# nRF52840.net
KiCad netlist of a schematic drawn in Altium Designer
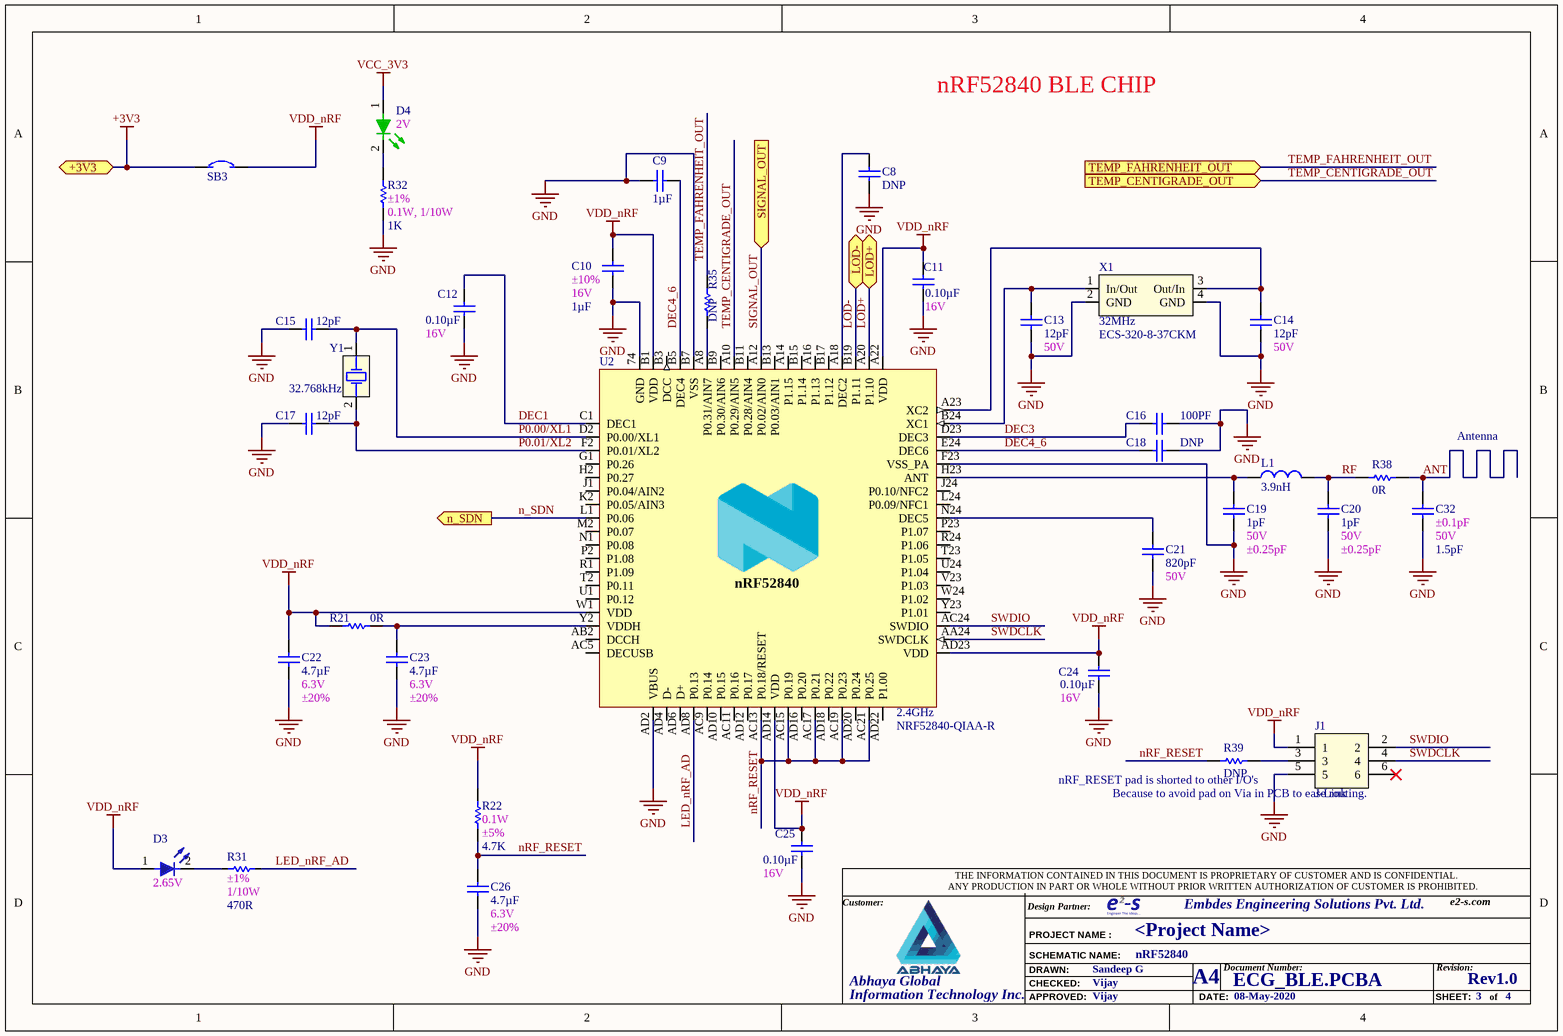
[diagram p0: nRF52840.SchDoc]

(export (version "E")
  (design (tool "Eeschema 10.0.6"))
  (components
    (comp (ref "C8")
      (value "DNP")
      (footprint "SMDC0402")
      (description "CAP CER 100PF 25V C0G/NP0 0402")
      (fields (field (name "MANUFACTURER") "KEMET") (field (name "VENDOR PART NUMBER") "399-1022-1-ND"))
      (libsource (lib "Master_ Library") (part "ECA100P0K25V0-SB"))
    )
    (comp (ref "C9")
      (value "1µF")
      (footprint "SMDC0402")
      (description "CAP CER 1UF 16V X5R 0402")
      (fields
        (field (name "MANUFACTURER") "Samsung Electro-Mechanics")
        (field (name "VENDOR PART NUMBER") "1276-1067-1-ND")
      )
      (libsource (lib "Integrated_Master_Library") (part "ECA1U00L16V0-SB"))
    )
    (comp (ref "C10")
      (value "1µF")
      (footprint "SMDC0402")
      (description "CAP CER 1UF 16V X5R 0402")
      (fields
        (field (name "MANUFACTURER") "Samsung Electro-Mechanics")
        (field (name "VENDOR PART NUMBER") "1276-1067-1-ND")
        (field (name "2ND AUXILIARY FIELD") "±10%")
        (field (name "1ST AUXILIARY FIELD") "16V")
      )
      (libsource (lib "Integrated_Master_Library") (part "ECA1U00L16V0-SB"))
    )
    (comp (ref "C11")
      (value "0.10µF")
      (footprint "SMDC0402")
      (description "CAP CER 0.1UF 16V X7R 0402")
      (fields
        (field (name "MANUFACTURER") "Samsung Electro-Mechanics America, Inc.")
        (field (name "MANUFACTURER PART NUMBER") "CL05B104KO5NNNC")
        (field (name "1ST AUXILIARY FIELD") "16V")
      )
      (libsource (lib "Master_ Library") (part "ECA0U10K16V0-1-SB"))
    )
    (comp (ref "C12")
      (value "0.10µF")
      (footprint "SMDC0402")
      (description "CAP CER 0.1UF 16V X7R 0402")
      (fields
        (field (name "MANUFACTURER") "Samsung Electro-Mechanics America, Inc.")
        (field (name "MANUFACTURER PART NUMBER") "CL05B104KO5NNNC")
        (field (name "1ST AUXILIARY FIELD") "16V")
      )
      (libsource (lib "Master_ Library") (part "ECA0U10K16V0-1-SB"))
    )
    (comp (ref "C13")
      (value "12pF")
      (footprint "SMDC0402")
      (description "CAP CER 12PF 50V C0G/NP0 0402")
      (fields
        (field (name "MANUFACTURER") "KEMET")
        (field (name "MANUFACTURER PART NUMBER") "CBR04C120J5GAC")
        (field (name "1ST AUXILIARY FIELD") "50V")
      )
      (libsource (lib "Integrated_Master_Library") (part "ECA12P0K50V0-SB"))
    )
    (comp (ref "C14")
      (value "12pF")
      (footprint "SMDC0402")
      (description "CAP CER 12PF 50V C0G/NP0 0402")
      (fields
        (field (name "MANUFACTURER") "KEMET")
        (field (name "MANUFACTURER PART NUMBER") "CBR04C120J5GAC")
        (field (name "1ST AUXILIARY FIELD") "50V")
      )
      (libsource (lib "Integrated_Master_Library") (part "ECA12P0K50V0-SB"))
    )
    (comp (ref "C15")
      (value "12pF")
      (footprint "SMDC0402")
      (description "CAP CER 12PF 50V C0G/NP0 0402")
      (fields
        (field (name "MANUFACTURER") "KEMET")
        (field (name "MANUFACTURER PART NUMBER") "CBR04C120J5GAC")
      )
      (libsource (lib "Master_ Library") (part "ECA12P0K50V0-SB"))
    )
    (comp (ref "C16")
      (value "100PF")
      (footprint "SMDC0402")
      (description "CAP CER 100PF 25V C0G/NP0 0402")
      (fields (field (name "MANUFACTURER") "KEMET") (field (name "VENDOR PART NUMBER") "399-1022-1-ND"))
      (libsource (lib "Master_ Library") (part "ECA100P0K25V0-SB"))
    )
    (comp (ref "C17")
      (value "12pF")
      (footprint "SMDC0402")
      (description "CAP CER 12PF 50V C0G/NP0 0402")
      (fields
        (field (name "MANUFACTURER") "KEMET")
        (field (name "MANUFACTURER PART NUMBER") "CBR04C120J5GAC")
      )
      (libsource (lib "Master_ Library") (part "ECA12P0K50V0-SB"))
    )
    (comp (ref "C18")
      (value "DNP")
      (footprint "SMDC0402")
      (description "CAP CER 100PF 25V C0G/NP0 0402")
      (fields (field (name "MANUFACTURER") "KEMET") (field (name "VENDOR PART NUMBER") "399-1022-1-ND"))
      (libsource (lib "Master_ Library") (part "ECA100P0K25V0-SB"))
    )
    (comp (ref "C19")
      (value "1pF")
      (footprint "SMDC0402")
      (description "CAP CER 1PF 50V C0G/NP0 0402")
      (fields
        (field (name "MANUFACTURER") "Samsung Electro-Mechanics")
        (field (name "MANUFACTURER PART NUMBER") "CL05C010CB5NNNC")
        (field (name "1ST AUXILIARY FIELD") "50V")
        (field (name "2ND AUXILIARY FIELD") "±0.25pF")
      )
      (libsource (lib "Wifi-Vista") (part "ECA1P00V50V0-SB"))
    )
    (comp (ref "C20")
      (value "1pF")
      (footprint "SMDC0402")
      (description "CAP CER 1PF 50V C0G/NP0 0402")
      (fields
        (field (name "MANUFACTURER") "Samsung Electro-Mechanics")
        (field (name "MANUFACTURER PART NUMBER") "CL05C010CB5NNNC")
        (field (name "1ST AUXILIARY FIELD") "50V")
        (field (name "2ND AUXILIARY FIELD") "±0.25pF")
      )
      (libsource (lib "Wifi-Vista") (part "ECA1P00V50V0-SB"))
    )
    (comp (ref "C21")
      (value "820pF")
      (footprint "SMDC0402")
      (description "CAP CER 820PF 50V C0G/NP0 0402")
      (fields
        (field (name "MANUFACTURER") "Samsung Electro-Mechanics")
        (field (name "MANUFACTURER PART NUMBER") "CL05C821JB5NNNC")
        (field (name "1ST AUXILIARY FIELD") "50V")
      )
      (libsource (lib "Master_ Library") (part "ECA820PK50V0-SB"))
    )
    (comp (ref "C22")
      (value "4.7µF")
      (footprint "SMDC0402")
      (description "CAP CER 4.7UF 6.3V X5R 0402")
      (fields
        (field (name "MANUFACTURER") "Murata Electronics North America")
        (field (name "MANUFACTURER PART NUMBER") "GRM155R60J475ME47D")
        (field (name "1ST AUXILIARY FIELD") "6.3V")
        (field (name "2ND AUXILIARY FIELD") "±20%")
      )
      (libsource (lib "Integrated_Master_Library") (part "ECA4U70N6V30-SB"))
    )
    (comp (ref "C23")
      (value "4.7µF")
      (footprint "SMDC0402")
      (description "CAP CER 4.7UF 6.3V X5R 0402")
      (fields
        (field (name "MANUFACTURER") "Murata Electronics North America")
        (field (name "MANUFACTURER PART NUMBER") "GRM155R60J475ME47D")
        (field (name "1ST AUXILIARY FIELD") "6.3V")
        (field (name "2ND AUXILIARY FIELD") "±20%")
      )
      (libsource (lib "Integrated_Master_Library") (part "ECA4U70N6V30-SB"))
    )
    (comp (ref "C24")
      (value "0.10µF")
      (footprint "SMDC0402")
      (description "CAP CER 0.1UF 16V X7R 0402")
      (fields
        (field (name "MANUFACTURER") "Samsung Electro-Mechanics America, Inc.")
        (field (name "MANUFACTURER PART NUMBER") "CL05B104KO5NNNC")
        (field (name "1ST AUXILIARY FIELD") "16V")
      )
      (libsource (lib "Master_ Library") (part "ECA0U10K16V0-1-SB"))
    )
    (comp (ref "C25")
      (value "0.10µF")
      (footprint "SMDC0402")
      (description "CAP CER 0.1UF 16V X7R 0402")
      (fields
        (field (name "MANUFACTURER") "Samsung Electro-Mechanics America, Inc.")
        (field (name "MANUFACTURER PART NUMBER") "CL05B104KO5NNNC")
        (field (name "1ST AUXILIARY FIELD") "16V")
      )
      (libsource (lib "Master_ Library") (part "ECA0U10K16V0-1-SB"))
    )
    (comp (ref "C26")
      (value "4.7µF")
      (footprint "SMDC0402")
      (description "CAP CER 4.7UF 6.3V X5R 0402")
      (fields
        (field (name "MANUFACTURER") "Murata Electronics North America")
        (field (name "MANUFACTURER PART NUMBER") "GRM155R60J475ME47D")
        (field (name "1ST AUXILIARY FIELD") "6.3V")
        (field (name "2ND AUXILIARY FIELD") "±20%")
      )
      (libsource (lib "Integrated_Master_Library") (part "ECA4U70N6V30-SB"))
    )
    (comp (ref "C32")
      (value "1.5pF")
      (footprint "SMDC0402")
      (description "CAP CER 1.5PF 50V NP0 0402")
      (fields
        (field (name "MANUFACTURER") "Murata Electronics North America")
        (field (name "VENDOR PART NUMBER") "490-8087-1-ND")
        (field (name "2ND AUXILIARY FIELD") "±0.1pF")
        (field (name "1ST AUXILIARY FIELD") "50V")
      )
      (libsource (lib "Integrated_Library (1)") (part "ECA1P50D50V0-SB"))
    )
    (comp (ref "D3")
      (value "LED BLUE CLEAR 2SMD")
      (footprint "SMDLED0603")
      (fields
        (field (name "MANUFACTURER") "Kingbright")
        (field (name "VENDOR PART NUMBER") "754-1933-1-ND")
        (field (name "MANUFACTURER PART NUMBER") "APT1608LVBC/D")
        (field (name "1ST AUXILIARY FIELD") "2.65V")
      )
      (libsource (lib "ECG_BLE") (part "ELDB2V652M00-SC"))
    )
    (comp (ref "D4")
      (value "LED GREEN CLEAR SMD")
      (footprint "SMDLED0603")
      (fields
        (field (name "MANUFACTURER") "Lite-On Inc.")
        (field (name "VENDOR PART NUMBER") "160-1446-1-ND")
        (field (name "1ST AUXILIARY FIELD") "2V")
        (field (name "MANUFACTURER PART NUMBER") "LTST-C191KGKT")
      )
      (libsource (lib "Master_ Library") (part "ELDG2V0020M0-SC"))
    )
    (comp (ref "J1")
      (value "J-LINK 6-PIN NEEDLE ADAPTER")
      (footprint "PRG_8.06.16 J-LINK 6-PIN NEEDLE ADAPTER")
      (fields
        (field (name "INTERNAL PART NUMBER") "EMS-8.06.16 J-LINK 6-PIN NEEDLE ADAPTER")
        (field (name "MANUFACTURER") "Segger Microcontroller Systems")
        (field (name "VENDOR PART NUMBER") "899-1051-ND")
        (field (name "1ST AUXILIARY FIELD") "J-Link")
      )
      (libsource (lib "Integrated_Master_Library") (part "EMS-8.06.16 J-LINK 6-PIN NEEDLE ADAPTER"))
    )
    (comp (ref "L1")
      (value "3.9nH")
      (footprint "SMDL0402")
      (description "FIXED IND 3.9NH 170MA 500 MOHM")
      (fields
        (field (name "MANUFACTURER PART NUMBER") "LQP15MN3N9B02D")
        (field (name "MANUFACTURER") "Murata Electronics North America")
      )
      (libsource (lib "Integrated_Master_Library") (part "EIN3N90T170M-SB"))
    )
    (comp (ref "R21")
      (value "0R")
      (footprint "SMDR0402")
      (description "RES SMD 0.0OHM JUMPER 1/10W 0402")
      (fields
        (field (name "MANUFACTURER") "Panasonic Electronic Components")
        (field (name "VENDOR PART NUMBER") "P0.0JCT-ND")
      )
      (libsource (lib "Integrated_Master_Library") (part "ERE0R00110-SB"))
    )
    (comp (ref "R22")
      (value "4.7K")
      (footprint "SMDR0402")
      (description "RES SMD 4.7K OHM 5% 1/10W 0402")
      (fields
        (field (name "MANUFACTURER PART NUMBER") "ERJ-2GEJ472X")
        (field (name "MANUFACTURER") "Panasonic Electronic Components")
        (field (name "1ST AUXILIARY FIELD") "0.1W")
        (field (name "2ND AUXILIARY FIELD") "±5%")
      )
      (libsource (lib "Integrated_Master_Library") (part "ERE4K70J110-SB"))
    )
    (comp (ref "R31")
      (value "470R")
      (footprint "SMDR0402")
      (description "RES SMD 470 OHM 1% 1/10W 0402")
      (fields
        (field (name "MANUFACTURER PART NUMBER") "ERJ-2RKF4700X")
        (field (name "MANUFACTURER") "Panasonic Electronic Components")
        (field (name "1ST AUXILIARY FIELD") "±1%")
        (field (name "2ND AUXILIARY FIELD") "1/10W")
      )
      (libsource (lib "Master_ Library") (part "ERE470RG110-SB"))
    )
    (comp (ref "R32")
      (value "1K")
      (footprint "SMDR0402")
      (description "RES SMD 1K OHM 1% 1/10W 0402")
      (fields
        (field (name "MANUFACTURER") "Panasonic Electronic Components")
        (field (name "VENDOR PART NUMBER") "P1.00KLCT-ND")
        (field (name "2ND AUXILIARY FIELD") "±1%")
        (field (name "1ST AUXILIARY FIELD") "0.1W, 1/10W")
      )
      (libsource (lib "Master_ Library") (part "ERE1K00G110-SB_1"))
    )
    (comp (ref "R35")
      (value "DNP")
      (footprint "SMDR0402")
      (description "RES SMD 0.0OHM JUMPER 1/10W 0402")
      (fields
        (field (name "MANUFACTURER") "Panasonic Electronic Components")
        (field (name "VENDOR PART NUMBER") "P0.0JCT-ND")
      )
      (libsource (lib "Integrated_Master_Library") (part "ERE0R00110-SB"))
    )
    (comp (ref "R38")
      (value "0R")
      (footprint "SMDR0402")
      (description "RES SMD 0.0OHM JUMPER 1/10W 0402")
      (fields
        (field (name "MANUFACTURER") "Panasonic Electronic Components")
        (field (name "VENDOR PART NUMBER") "P0.0JCT-ND")
      )
      (libsource (lib "Integrated_Master_Library") (part "ERE0R00110-SB"))
    )
    (comp (ref "R39")
      (value "DNP")
      (footprint "SMDR0402")
      (description "RES SMD 0.0OHM JUMPER 1/10W 0402")
      (fields
        (field (name "MANUFACTURER") "Panasonic Electronic Components")
        (field (name "VENDOR PART NUMBER") "P0.0JCT-ND")
      )
      (libsource (lib "Integrated_Master_Library") (part "ERE0R00110-SB"))
    )
    (comp (ref "SB3")
      (value "EMS_SB0805")
      (footprint "SB_0805")
      (libsource (lib "Masterlib_auto") (part "EMS_SB0805"))
    )
    (comp (ref "U2")
      (value "NRF52840-QIAA-R")
      (footprint "AQFN50P700X700X85_HS-74N")
      (description "IC RF TXRX+MCU 802.15.4 73VFQFN")
      (fields
        (field (name "INTERNAL PART NUMBER") "EICNSVFQFN-73-1863")
        (field (name "MANUFACTURER") "Nordic Semiconductor ASA")
        (field (name "1ST AUXILIARY FIELD") "2.4GHz")
      )
      (libsource (lib "Master_ Library") (part "EICNSVFQFN-73-1863"))
    )
    (comp (ref "X1")
      (value "ECS-320-8-37CKM")
      (footprint "XTAL200X160X50-4N")
      (description "CRYSTAL 32.0000MHZ 8PF SMD")
      (fields
        (field (name "INTERNAL PART NUMBER") "EMS-ECS-320-8-37CKM")
        (field (name "MANUFACTURER") "ECS Inc.")
        (field (name "1ST AUXILIARY FIELD") "32MHz")
      )
      (libsource (lib "Integrated_Master_Library") (part "EMS-ECS-320-8-37CKM"))
    )
    (comp (ref "Y1")
      (value "CRYSTAL 32.7680KHZ 12.5PF SMD")
      (footprint "XTAL325X155X80N")
      (fields
        (field (name "INTERNAL PART NUMBER") "EMS-ABS07-32.768KHZ-T")
        (field (name "MANUFACTURER") "Abracon LLC")
        (field (name "VENDOR PART NUMBER") "535-9542-1-ND")
        (field (name "1ST AUXILIARY FIELD") "32.768kHz")
      )
      (libsource (lib "Master_ Library") (part "EMS-ABS07-32.768KHZ-T"))
    )
  )
  (nets
    (net (code "1") (name "+3V3") (class "Default")
      (node (ref "SB3") (pin "1") (pinfunction "1_1") (pintype "passive"))
    )
    (net (code "2") (name "/ANT") (class "Default")
      (node (ref "C32") (pin "2") (pinfunction "2_2") (pintype "passive"))
      (node (ref "R38") (pin "2") (pinfunction "2_2") (pintype "passive"))
    )
    (net (code "3") (name "/DEC1") (class "Default")
      (node (ref "C12") (pin "2") (pinfunction "2_2") (pintype "passive"))
      (node (ref "U2") (pin "C1") (pinfunction "DEC1_C1") (pintype "power_in"))
    )
    (net (code "4") (name "/DEC3") (class "Default")
      (node (ref "C16") (pin "1") (pinfunction "1_1") (pintype "passive"))
      (node (ref "U2") (pin "D23") (pinfunction "DEC3_D23") (pintype "power_in"))
    )
    (net (code "5") (name "/DEC4_6") (class "Default")
      (node (ref "C18") (pin "1") (pinfunction "1_1") (pintype "passive"))
      (node (ref "C9") (pin "2") (pinfunction "2_2") (pintype "passive"))
      (node (ref "U2") (pin "B5") (pinfunction "DEC4_B5") (pintype "power_in"))
      (node (ref "U2") (pin "E24") (pinfunction "DEC6_E24") (pintype "power_in"))
    )
    (net (code "6") (name "/LED_nRF_AD") (class "Default")
      (node (ref "R31") (pin "1") (pinfunction "1_1") (pintype "passive"))
      (node (ref "U2") (pin "AD8") (pinfunction "P0.13_AD8") (pintype "bidirectional"))
    )
    (net (code "7") (name "/LOD+") (class "Default")
      (node (ref "U2") (pin "A20") (pinfunction "P1.10_A20") (pintype "bidirectional"))
    )
    (net (code "8") (name "/LOD-") (class "Default")
      (node (ref "U2") (pin "B19") (pinfunction "P1.11_B19") (pintype "bidirectional"))
    )
    (net (code "9") (name "/P0.00{slash}XL1") (class "Default")
      (node (ref "C15") (pin "2") (pinfunction "2_2") (pintype "passive"))
      (node (ref "U2") (pin "D2") (pinfunction "P0.00/XL1_D2") (pintype "bidirectional"))
      (node (ref "Y1") (pin "1") (pinfunction "1_1") (pintype "passive"))
    )
    (net (code "10") (name "/P0.01{slash}XL2") (class "Default")
      (node (ref "C17") (pin "2") (pinfunction "2_2") (pintype "passive"))
      (node (ref "U2") (pin "F2") (pinfunction "P0.01/XL2_F2") (pintype "bidirectional"))
      (node (ref "Y1") (pin "2") (pinfunction "2_2") (pintype "passive"))
    )
    (net (code "11") (name "/RF") (class "Default")
      (node (ref "C20") (pin "2") (pinfunction "2_2") (pintype "passive"))
      (node (ref "L1") (pin "2") (pinfunction "2_2") (pintype "passive"))
      (node (ref "R38") (pin "1") (pinfunction "1_1") (pintype "passive"))
    )
    (net (code "12") (name "/SIGNAL_OUT") (class "Default")
      (node (ref "U2") (pin "A12") (pinfunction "P0.02/AIN0_A12") (pintype "bidirectional"))
    )
    (net (code "13") (name "/SWDCLK") (class "Default")
      (node (ref "J1") (pin "4") (pinfunction "4_4") (pintype "passive"))
      (node (ref "U2") (pin "AA24") (pinfunction "SWDCLK_AA24") (pintype "input"))
    )
    (net (code "14") (name "/SWDIO") (class "Default")
      (node (ref "J1") (pin "2") (pinfunction "2_2") (pintype "passive"))
      (node (ref "U2") (pin "AC24") (pinfunction "SWDIO_AC24") (pintype "bidirectional"))
    )
    (net (code "15") (name "/TEMP_CENTIGRADE_OUT") (class "Default")
      (node (ref "U2") (pin "A10") (pinfunction "P0.29/AIN5_A10") (pintype "bidirectional"))
    )
    (net (code "16") (name "/TEMP_FAHRENHEIT_OUT") (class "Default")
      (node (ref "R35") (pin "2") (pinfunction "2_2") (pintype "passive"))
    )
    (net (code "17") (name "/nRF_RESET") (class "Default")
      (node (ref "C26") (pin "2") (pinfunction "2_2") (pintype "passive"))
      (node (ref "R22") (pin "1") (pinfunction "1_1") (pintype "passive"))
      (node (ref "R39") (pin "1") (pinfunction "1_1") (pintype "passive"))
      (node (ref "U2") (pin "AC13") (pinfunction "P0.18/RESET_AC13") (pintype "bidirectional"))
      (node (ref "U2") (pin "AC15") (pinfunction "P0.19_AC15") (pintype "bidirectional"))
      (node (ref "U2") (pin "AC17") (pinfunction "P0.21_AC17") (pintype "bidirectional"))
      (node (ref "U2") (pin "AC19") (pinfunction "P0.23_AC19") (pintype "bidirectional"))
      (node (ref "U2") (pin "AC21") (pinfunction "P0.25_AC21") (pintype "bidirectional"))
    )
    (net (code "18") (name "/n_SDN") (class "Default")
      (node (ref "U2") (pin "L1") (pinfunction "P0.06_L1") (pintype "bidirectional"))
    )
    (net (code "19") (name "GND") (class "Default")
      (node (ref "C10") (pin "1") (pinfunction "1_1") (pintype "passive"))
      (node (ref "C11") (pin "1") (pinfunction "1_1") (pintype "passive"))
      (node (ref "C12") (pin "1") (pinfunction "1_1") (pintype "passive"))
      (node (ref "C13") (pin "1") (pinfunction "1_1") (pintype "passive"))
      (node (ref "C14") (pin "1") (pinfunction "1_1") (pintype "passive"))
      (node (ref "C15") (pin "1") (pinfunction "1_1") (pintype "passive"))
      (node (ref "C16") (pin "2") (pinfunction "2_2") (pintype "passive"))
      (node (ref "C17") (pin "1") (pinfunction "1_1") (pintype "passive"))
      (node (ref "C18") (pin "2") (pinfunction "2_2") (pintype "passive"))
      (node (ref "C19") (pin "1") (pinfunction "1_1") (pintype "passive"))
      (node (ref "C20") (pin "1") (pinfunction "1_1") (pintype "passive"))
      (node (ref "C21") (pin "1") (pinfunction "1_1") (pintype "passive"))
      (node (ref "C22") (pin "1") (pinfunction "1_1") (pintype "passive"))
      (node (ref "C23") (pin "1") (pinfunction "1_1") (pintype "passive"))
      (node (ref "C24") (pin "1") (pinfunction "1_1") (pintype "passive"))
      (node (ref "C25") (pin "1") (pinfunction "1_1") (pintype "passive"))
      (node (ref "C26") (pin "1") (pinfunction "1_1") (pintype "passive"))
      (node (ref "C32") (pin "1") (pinfunction "1_1") (pintype "passive"))
      (node (ref "C8") (pin "2") (pinfunction "2_2") (pintype "passive"))
      (node (ref "C9") (pin "1") (pinfunction "1_1") (pintype "passive"))
      (node (ref "J1") (pin "5") (pinfunction "5_5") (pintype "passive"))
      (node (ref "R32") (pin "2") (pinfunction "2_2") (pintype "passive"))
      (node (ref "U2") (pin "74") (pinfunction "GND_74") (pintype "passive"))
      (node (ref "U2") (pin "AD2") (pinfunction "VBUS_AD2") (pintype "power_in"))
      (node (ref "U2") (pin "B7") (pinfunction "VSS_B7") (pintype "power_in"))
      (node (ref "U2") (pin "F23") (pinfunction "VSS_PA_F23") (pintype "power_in"))
      (node (ref "X1") (pin "2") (pinfunction "GND_2") (pintype "power_in"))
      (node (ref "X1") (pin "4") (pinfunction "GND_4") (pintype "passive"))
    )
    (net (code "20") (name "Net-(D3-K)") (class "Default")
      (node (ref "D3") (pin "2") (pinfunction "K_2") (pintype "passive"))
      (node (ref "R31") (pin "2") (pinfunction "2_2") (pintype "passive"))
    )
    (net (code "21") (name "Net-(D4-K)") (class "Default")
      (node (ref "D4") (pin "2") (pinfunction "K_2") (pintype "passive"))
      (node (ref "R32") (pin "1") (pinfunction "1_1") (pintype "passive"))
    )
    (net (code "22") (name "Net-(J1-Pad3)") (class "Default")
      (node (ref "J1") (pin "3") (pinfunction "3_3") (pintype "passive"))
      (node (ref "R39") (pin "2") (pinfunction "2_2") (pintype "passive"))
    )
    (net (code "23") (name "Net-(U2-ANT)") (class "Default")
      (node (ref "C19") (pin "2") (pinfunction "2_2") (pintype "passive"))
      (node (ref "L1") (pin "1") (pinfunction "1_1") (pintype "passive"))
      (node (ref "U2") (pin "H23") (pinfunction "ANT_H23") (pintype "bidirectional"))
    )
    (net (code "24") (name "Net-(U2-DEC2)") (class "Default")
      (node (ref "C8") (pin "1") (pinfunction "1_1") (pintype "passive"))
      (node (ref "U2") (pin "A18") (pinfunction "DEC2_A18") (pintype "power_in"))
    )
    (net (code "25") (name "Net-(U2-DEC5)") (class "Default")
      (node (ref "C21") (pin "2") (pinfunction "2_2") (pintype "passive"))
      (node (ref "U2") (pin "N24") (pinfunction "DEC5_N24") (pintype "power_in"))
    )
    (net (code "26") (name "Net-(U2-P0.31{slash}AIN7)") (class "Default")
      (node (ref "R35") (pin "1") (pinfunction "1_1") (pintype "passive"))
      (node (ref "U2") (pin "A8") (pinfunction "P0.31/AIN7_A8") (pintype "bidirectional"))
    )
    (net (code "27") (name "Net-(U2-VDDH)") (class "Default")
      (node (ref "C23") (pin "2") (pinfunction "2_2") (pintype "passive"))
      (node (ref "R21") (pin "2") (pinfunction "2_2") (pintype "passive"))
      (node (ref "U2") (pin "Y2") (pinfunction "VDDH_Y2") (pintype "power_in"))
    )
    (net (code "28") (name "Net-(U2-XC1)") (class "Default")
      (node (ref "C13") (pin "2") (pinfunction "2_2") (pintype "passive"))
      (node (ref "U2") (pin "B24") (pinfunction "XC1_B24") (pintype "input"))
      (node (ref "X1") (pin "1") (pinfunction "In/Out_1") (pintype "bidirectional"))
    )
    (net (code "29") (name "Net-(U2-XC2)") (class "Default")
      (node (ref "C14") (pin "2") (pinfunction "2_2") (pintype "passive"))
      (node (ref "U2") (pin "A23") (pinfunction "XC2_A23") (pintype "output"))
      (node (ref "X1") (pin "3") (pinfunction "Out/In_3") (pintype "bidirectional"))
    )
    (net (code "30") (name "VCC_3V3") (class "Default")
      (node (ref "D4") (pin "1") (pinfunction "A_1") (pintype "passive"))
    )
    (net (code "31") (name "VDD_nRF") (class "Default")
      (node (ref "C10") (pin "2") (pinfunction "2_2") (pintype "passive"))
      (node (ref "C11") (pin "2") (pinfunction "2_2") (pintype "passive"))
      (node (ref "C22") (pin "2") (pinfunction "2_2") (pintype "passive"))
      (node (ref "C24") (pin "2") (pinfunction "2_2") (pintype "passive"))
      (node (ref "C25") (pin "2") (pinfunction "2_2") (pintype "passive"))
      (node (ref "D3") (pin "1") (pinfunction "A_1") (pintype "passive"))
      (node (ref "J1") (pin "1") (pinfunction "1_1") (pintype "passive"))
      (node (ref "R21") (pin "1") (pinfunction "1_1") (pintype "passive"))
      (node (ref "R22") (pin "2") (pinfunction "2_2") (pintype "passive"))
      (node (ref "SB3") (pin "2") (pinfunction "2_2") (pintype "passive"))
      (node (ref "U2") (pin "A22") (pinfunction "VDD_A22") (pintype "power_in"))
      (node (ref "U2") (pin "AD14") (pinfunction "VDD_AD14") (pintype "power_in"))
      (node (ref "U2") (pin "AD23") (pinfunction "VDD_AD23") (pintype "power_in"))
      (node (ref "U2") (pin "B1") (pinfunction "VDD_B1") (pintype "power_in"))
      (node (ref "U2") (pin "W1") (pinfunction "VDD_W1") (pintype "power_in"))
    )
    (net (code "32") (name "unconnected-(J1-Pad6)") (class "Default")
      (node (ref "J1") (pin "6") (pinfunction "6_6") (pintype "passive+no_connect"))
    )
    (net (code "33") (name "unconnected-(U2-D+-PadAD6)") (class "Default")
      (node (ref "U2") (pin "AD6") (pinfunction "D+_AD6") (pintype "bidirectional"))
    )
    (net (code "34") (name "unconnected-(U2-D--PadAD4)") (class "Default")
      (node (ref "U2") (pin "AD4") (pinfunction "D-_AD4") (pintype "bidirectional"))
    )
    (net (code "35") (name "unconnected-(U2-DCC-PadB3)") (class "Default")
      (node (ref "U2") (pin "B3") (pinfunction "DCC_B3") (pintype "output"))
    )
    (net (code "36") (name "unconnected-(U2-DCCH-PadAB2)") (class "Default")
      (node (ref "U2") (pin "AB2") (pinfunction "DCCH_AB2") (pintype "power_in"))
    )
    (net (code "37") (name "unconnected-(U2-DECUSB-PadAC5)") (class "Default")
      (node (ref "U2") (pin "AC5") (pinfunction "DECUSB_AC5") (pintype "power_in"))
    )
    (net (code "38") (name "unconnected-(U2-P0.03{slash}AIN1-PadB13)") (class "Default")
      (node (ref "U2") (pin "B13") (pinfunction "P0.03/AIN1_B13") (pintype "bidirectional"))
    )
    (net (code "39") (name "unconnected-(U2-P0.04{slash}AIN2-PadJ1)") (class "Default")
      (node (ref "U2") (pin "J1") (pinfunction "P0.04/AIN2_J1") (pintype "bidirectional"))
    )
    (net (code "40") (name "unconnected-(U2-P0.05{slash}AIN3-PadK2)") (class "Default")
      (node (ref "U2") (pin "K2") (pinfunction "P0.05/AIN3_K2") (pintype "bidirectional"))
    )
    (net (code "41") (name "unconnected-(U2-P0.07-PadM2)") (class "Default")
      (node (ref "U2") (pin "M2") (pinfunction "P0.07_M2") (pintype "bidirectional"))
    )
    (net (code "42") (name "unconnected-(U2-P0.08-PadN1)") (class "Default")
      (node (ref "U2") (pin "N1") (pinfunction "P0.08_N1") (pintype "bidirectional"))
    )
    (net (code "43") (name "unconnected-(U2-P0.09{slash}NFC1-PadL24)") (class "Default")
      (node (ref "U2") (pin "L24") (pinfunction "P0.09/NFC1_L24") (pintype "bidirectional"))
    )
    (net (code "44") (name "unconnected-(U2-P0.10{slash}NFC2-PadJ24)") (class "Default")
      (node (ref "U2") (pin "J24") (pinfunction "P0.10/NFC2_J24") (pintype "bidirectional"))
    )
    (net (code "45") (name "unconnected-(U2-P0.11-PadT2)") (class "Default")
      (node (ref "U2") (pin "T2") (pinfunction "P0.11_T2") (pintype "bidirectional"))
    )
    (net (code "46") (name "unconnected-(U2-P0.12-PadU1)") (class "Default")
      (node (ref "U2") (pin "U1") (pinfunction "P0.12_U1") (pintype "bidirectional"))
    )
    (net (code "47") (name "unconnected-(U2-P0.14-PadAC9)") (class "Default")
      (node (ref "U2") (pin "AC9") (pinfunction "P0.14_AC9") (pintype "bidirectional"))
    )
    (net (code "48") (name "unconnected-(U2-P0.15-PadAD10)") (class "Default")
      (node (ref "U2") (pin "AD10") (pinfunction "P0.15_AD10") (pintype "bidirectional"))
    )
    (net (code "49") (name "unconnected-(U2-P0.16-PadAC11)") (class "Default")
      (node (ref "U2") (pin "AC11") (pinfunction "P0.16_AC11") (pintype "bidirectional"))
    )
    (net (code "50") (name "unconnected-(U2-P0.17-PadAD12)") (class "Default")
      (node (ref "U2") (pin "AD12") (pinfunction "P0.17_AD12") (pintype "bidirectional"))
    )
    (net (code "51") (name "unconnected-(U2-P0.20-PadAD16)") (class "Default")
      (node (ref "U2") (pin "AD16") (pinfunction "P0.20_AD16") (pintype "bidirectional"))
    )
    (net (code "52") (name "unconnected-(U2-P0.22-PadAD18)") (class "Default")
      (node (ref "U2") (pin "AD18") (pinfunction "P0.22_AD18") (pintype "bidirectional"))
    )
    (net (code "53") (name "unconnected-(U2-P0.24-PadAD20)") (class "Default")
      (node (ref "U2") (pin "AD20") (pinfunction "P0.24_AD20") (pintype "bidirectional"))
    )
    (net (code "54") (name "unconnected-(U2-P0.26-PadG1)") (class "Default")
      (node (ref "U2") (pin "G1") (pinfunction "P0.26_G1") (pintype "bidirectional"))
    )
    (net (code "55") (name "unconnected-(U2-P0.27-PadH2)") (class "Default")
      (node (ref "U2") (pin "H2") (pinfunction "P0.27_H2") (pintype "bidirectional"))
    )
    (net (code "56") (name "unconnected-(U2-P0.28{slash}AIN4-PadB11)") (class "Default")
      (node (ref "U2") (pin "B11") (pinfunction "P0.28/AIN4_B11") (pintype "bidirectional"))
    )
    (net (code "57") (name "unconnected-(U2-P0.30{slash}AIN6-PadB9)") (class "Default")
      (node (ref "U2") (pin "B9") (pinfunction "P0.30/AIN6_B9") (pintype "bidirectional"))
    )
    (net (code "58") (name "unconnected-(U2-P1.00-PadAD22)") (class "Default")
      (node (ref "U2") (pin "AD22") (pinfunction "P1.00_AD22") (pintype "bidirectional"))
    )
    (net (code "59") (name "unconnected-(U2-P1.01-PadY23)") (class "Default")
      (node (ref "U2") (pin "Y23") (pinfunction "P1.01_Y23") (pintype "bidirectional"))
    )
    (net (code "60") (name "unconnected-(U2-P1.02-PadW24)") (class "Default")
      (node (ref "U2") (pin "W24") (pinfunction "P1.02_W24") (pintype "bidirectional"))
    )
    (net (code "61") (name "unconnected-(U2-P1.03-PadV23)") (class "Default")
      (node (ref "U2") (pin "V23") (pinfunction "P1.03_V23") (pintype "bidirectional"))
    )
    (net (code "62") (name "unconnected-(U2-P1.04-PadU24)") (class "Default")
      (node (ref "U2") (pin "U24") (pinfunction "P1.04_U24") (pintype "bidirectional"))
    )
    (net (code "63") (name "unconnected-(U2-P1.05-PadT23)") (class "Default")
      (node (ref "U2") (pin "T23") (pinfunction "P1.05_T23") (pintype "bidirectional"))
    )
    (net (code "64") (name "unconnected-(U2-P1.06-PadR24)") (class "Default")
      (node (ref "U2") (pin "R24") (pinfunction "P1.06_R24") (pintype "bidirectional"))
    )
    (net (code "65") (name "unconnected-(U2-P1.07-PadP23)") (class "Default")
      (node (ref "U2") (pin "P23") (pinfunction "P1.07_P23") (pintype "bidirectional"))
    )
    (net (code "66") (name "unconnected-(U2-P1.08-PadP2)") (class "Default")
      (node (ref "U2") (pin "P2") (pinfunction "P1.08_P2") (pintype "bidirectional"))
    )
    (net (code "67") (name "unconnected-(U2-P1.09-PadR1)") (class "Default")
      (node (ref "U2") (pin "R1") (pinfunction "P1.09_R1") (pintype "bidirectional"))
    )
    (net (code "68") (name "unconnected-(U2-P1.12-PadB17)") (class "Default")
      (node (ref "U2") (pin "B17") (pinfunction "P1.12_B17") (pintype "bidirectional"))
    )
    (net (code "69") (name "unconnected-(U2-P1.13-PadA16)") (class "Default")
      (node (ref "U2") (pin "A16") (pinfunction "P1.13_A16") (pintype "bidirectional"))
    )
    (net (code "70") (name "unconnected-(U2-P1.14-PadB15)") (class "Default")
      (node (ref "U2") (pin "B15") (pinfunction "P1.14_B15") (pintype "bidirectional"))
    )
    (net (code "71") (name "unconnected-(U2-P1.15-PadA14)") (class "Default")
      (node (ref "U2") (pin "A14") (pinfunction "P1.15_A14") (pintype "bidirectional"))
    )
  )
)
